# Audio_Board_Breakout.net
KiCad netlist of a schematic drawn in Altium Designer
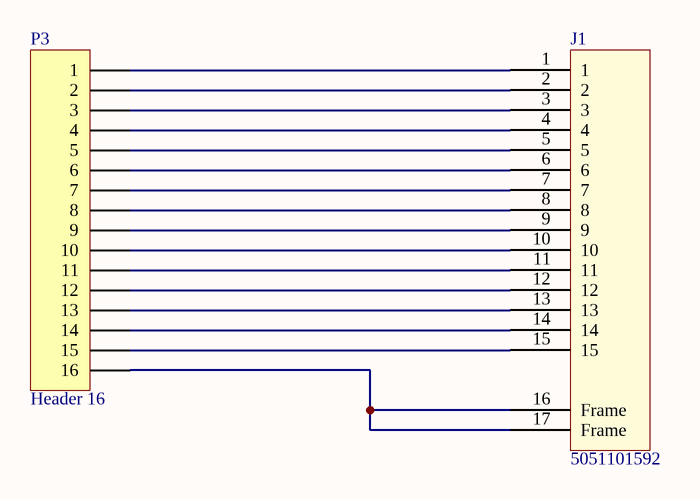
[diagram p0: Audio Board Breakout.SchDoc]

(export (version "E")
  (design (tool "Eeschema 10.0.6"))
  (components
    (comp (ref "J1")
      (value "5051101592")
      (footprint "5051101592")
      (libsource (lib "KBuchka-IntLib") (part "5051101592"))
    )
    (comp (ref "P3")
      (value "Header 16")
      (footprint "HDR1X16")
      (description "Header, 16-Pin")
      (fields (field (name "PUBLISHER") "Altium Limited"))
      (libsource (lib "Miscellaneous Connectors") (part "Header 16"))
    )
  )
  (nets
    (net (code "1") (name "Net-(J1-Frame-Pad16)") (class "Default")
      (node (ref "J1") (pin "16") (pinfunction "Frame_16") (pintype "passive"))
      (node (ref "J1") (pin "17") (pinfunction "Frame_17") (pintype "passive"))
      (node (ref "P3") (pin "16") (pinfunction "16_16") (pintype "passive"))
    )
    (net (code "2") (name "Net-(J1-Pad1)") (class "Default")
      (node (ref "J1") (pin "1") (pinfunction "1_1") (pintype "passive"))
      (node (ref "P3") (pin "1") (pinfunction "1_1") (pintype "passive"))
    )
    (net (code "3") (name "Net-(J1-Pad2)") (class "Default")
      (node (ref "J1") (pin "2") (pinfunction "2_2") (pintype "passive"))
      (node (ref "P3") (pin "2") (pinfunction "2_2") (pintype "passive"))
    )
    (net (code "4") (name "Net-(J1-Pad3)") (class "Default")
      (node (ref "J1") (pin "3") (pinfunction "3_3") (pintype "passive"))
      (node (ref "P3") (pin "3") (pinfunction "3_3") (pintype "passive"))
    )
    (net (code "5") (name "Net-(J1-Pad4)") (class "Default")
      (node (ref "J1") (pin "4") (pinfunction "4_4") (pintype "passive"))
      (node (ref "P3") (pin "4") (pinfunction "4_4") (pintype "passive"))
    )
    (net (code "6") (name "Net-(J1-Pad5)") (class "Default")
      (node (ref "J1") (pin "5") (pinfunction "5_5") (pintype "passive"))
      (node (ref "P3") (pin "5") (pinfunction "5_5") (pintype "passive"))
    )
    (net (code "7") (name "Net-(J1-Pad6)") (class "Default")
      (node (ref "J1") (pin "6") (pinfunction "6_6") (pintype "passive"))
      (node (ref "P3") (pin "6") (pinfunction "6_6") (pintype "passive"))
    )
    (net (code "8") (name "Net-(J1-Pad7)") (class "Default")
      (node (ref "J1") (pin "7") (pinfunction "7_7") (pintype "passive"))
      (node (ref "P3") (pin "7") (pinfunction "7_7") (pintype "passive"))
    )
    (net (code "9") (name "Net-(J1-Pad8)") (class "Default")
      (node (ref "J1") (pin "8") (pinfunction "8_8") (pintype "passive"))
      (node (ref "P3") (pin "8") (pinfunction "8_8") (pintype "passive"))
    )
    (net (code "10") (name "Net-(J1-Pad9)") (class "Default")
      (node (ref "J1") (pin "9") (pinfunction "9_9") (pintype "passive"))
      (node (ref "P3") (pin "9") (pinfunction "9_9") (pintype "passive"))
    )
    (net (code "11") (name "Net-(J1-Pad10)") (class "Default")
      (node (ref "J1") (pin "10") (pinfunction "10_10") (pintype "passive"))
      (node (ref "P3") (pin "10") (pinfunction "10_10") (pintype "passive"))
    )
    (net (code "12") (name "Net-(J1-Pad11)") (class "Default")
      (node (ref "J1") (pin "11") (pinfunction "11_11") (pintype "passive"))
      (node (ref "P3") (pin "11") (pinfunction "11_11") (pintype "passive"))
    )
    (net (code "13") (name "Net-(J1-Pad12)") (class "Default")
      (node (ref "J1") (pin "12") (pinfunction "12_12") (pintype "passive"))
      (node (ref "P3") (pin "12") (pinfunction "12_12") (pintype "passive"))
    )
    (net (code "14") (name "Net-(J1-Pad13)") (class "Default")
      (node (ref "J1") (pin "13") (pinfunction "13_13") (pintype "passive"))
      (node (ref "P3") (pin "13") (pinfunction "13_13") (pintype "passive"))
    )
    (net (code "15") (name "Net-(J1-Pad14)") (class "Default")
      (node (ref "J1") (pin "14") (pinfunction "14_14") (pintype "passive"))
      (node (ref "P3") (pin "14") (pinfunction "14_14") (pintype "passive"))
    )
    (net (code "16") (name "Net-(J1-Pad15)") (class "Default")
      (node (ref "J1") (pin "15") (pinfunction "15_15") (pintype "passive"))
      (node (ref "P3") (pin "15") (pinfunction "15_15") (pintype "passive"))
    )
  )
)
